# Microcontroller_Power.net
KiCad netlist of a schematic drawn in Altium Designer
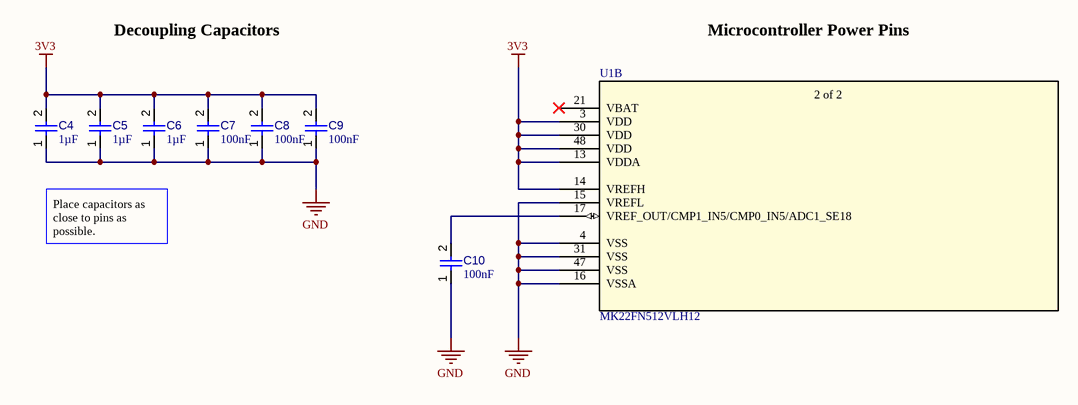
[diagram p0: Microcontroller_Power.SchDoc]

(export (version "E")
  (design (tool "Eeschema 10.0.6"))
  (components
    (comp (ref "C4")
      (value "1µF")
      (footprint "CAPC0805(2012)145_L")
      (description "Chip Capacitor, 1µF +/-20%, 25V, 0805, Thickness 1.45 mm")
      (fields (field (name "TOLERANCE") "10%") (field (name "Comment") "Capacitor 1µF +/-20% 25V 0805"))
      (libsource (lib "James Cook University") (part "CAP-NP-2"))
    )
    (comp (ref "C5")
      (value "1µF")
      (footprint "CAPC0805(2012)145_L")
      (description "Chip Capacitor, 1µF +/-20%, 25V, 0805, Thickness 1.45 mm")
      (fields (field (name "TOLERANCE") "10%") (field (name "Comment") "Capacitor 1µF +/-20% 25V 0805"))
      (libsource (lib "James Cook University") (part "CAP-NP-2"))
    )
    (comp (ref "C6")
      (value "1µF")
      (footprint "CAPC0805(2012)145_L")
      (description "Chip Capacitor, 1µF +/-20%, 25V, 0805, Thickness 1.45 mm")
      (fields (field (name "TOLERANCE") "10%") (field (name "Comment") "Capacitor 1µF +/-20% 25V 0805"))
      (libsource (lib "James Cook University") (part "CAP-NP-2"))
    )
    (comp (ref "C7")
      (value "100nF")
      (footprint "CAPC0805(2012)145_L")
      (description "Chip Capacitor, 100nF +/-20%, 25V, 0805, Thickness 1.45 mm")
      (fields (field (name "TOLERANCE") "10%") (field (name "Comment") "Capacitor 100nF +/-20% 25V 0805"))
      (libsource (lib "James Cook University") (part "CAP-NP-2"))
    )
    (comp (ref "C8")
      (value "100nF")
      (footprint "CAPC0805(2012)145_L")
      (description "Chip Capacitor, 100nF +/-20%, 25V, 0805, Thickness 1.45 mm")
      (fields (field (name "TOLERANCE") "10%") (field (name "Comment") "Capacitor 100nF +/-20% 25V 0805"))
      (libsource (lib "James Cook University") (part "CAP-NP-2"))
    )
    (comp (ref "C9")
      (value "100nF")
      (footprint "CAPC0805(2012)145_L")
      (description "Chip Capacitor, 100nF +/-20%, 25V, 0805, Thickness 1.45 mm")
      (fields (field (name "TOLERANCE") "10%") (field (name "Comment") "Capacitor 100nF +/-20% 25V 0805"))
      (libsource (lib "James Cook University") (part "CAP-NP-2"))
    )
    (comp (ref "C10")
      (value "100nF")
      (footprint "CAPC0805(2012)145_L")
      (description "Chip Capacitor, 100nF +/-20%, 25V, 0805, Thickness 1.45 mm")
      (fields (field (name "TOLERANCE") "10%") (field (name "Comment") "Capacitor 100nF +/-20% 25V 0805"))
      (libsource (lib "James Cook University") (part "CAP-NP-2"))
    )
    (comp (ref "U1")
      (value "MK22FN512VLH12")
      (footprint "LQFP-64_10X10X1.6_NXP")
      (description "No Description Available")
      (fields (field (name "COPYRIGHT") "Copyright (C) 2016 Accelerated Designs. All rights reserved"))
      (libsource (lib "MK22FN512VLH12") (part "MK22FN512VLH12"))
    )
  )
  (nets
    (net (code "1") (name "3V3") (class "Default")
      (node (ref "C4") (pin "2") (pinfunction "2_2") (pintype "passive"))
      (node (ref "C5") (pin "2") (pinfunction "2_2") (pintype "passive"))
      (node (ref "C6") (pin "2") (pinfunction "2_2") (pintype "passive"))
      (node (ref "C7") (pin "2") (pinfunction "2_2") (pintype "passive"))
      (node (ref "C8") (pin "2") (pinfunction "2_2") (pintype "passive"))
      (node (ref "C9") (pin "2") (pinfunction "2_2") (pintype "passive"))
      (node (ref "U1") (pin "13") (pinfunction "VDDA_13") (pintype "power_in"))
      (node (ref "U1") (pin "14") (pinfunction "VREFH_14") (pintype "power_in"))
      (node (ref "U1") (pin "3") (pinfunction "VDD_3") (pintype "power_in"))
      (node (ref "U1") (pin "30") (pinfunction "VDD_30") (pintype "power_in"))
      (node (ref "U1") (pin "48") (pinfunction "VDD_48") (pintype "power_in"))
    )
    (net (code "2") (name "GND") (class "Default")
      (node (ref "C10") (pin "1") (pinfunction "1_1") (pintype "passive"))
      (node (ref "C4") (pin "1") (pinfunction "1_1") (pintype "passive"))
      (node (ref "C5") (pin "1") (pinfunction "1_1") (pintype "passive"))
      (node (ref "C6") (pin "1") (pinfunction "1_1") (pintype "passive"))
      (node (ref "C7") (pin "1") (pinfunction "1_1") (pintype "passive"))
      (node (ref "C8") (pin "1") (pinfunction "1_1") (pintype "passive"))
      (node (ref "C9") (pin "1") (pinfunction "1_1") (pintype "passive"))
      (node (ref "U1") (pin "15") (pinfunction "VREFL_15") (pintype "power_in"))
      (node (ref "U1") (pin "16") (pinfunction "VSSA_16") (pintype "power_in"))
      (node (ref "U1") (pin "31") (pinfunction "VSS_31") (pintype "power_in"))
      (node (ref "U1") (pin "4") (pinfunction "VSS_4") (pintype "power_in"))
      (node (ref "U1") (pin "47") (pinfunction "VSS_47") (pintype "power_in"))
    )
    (net (code "3") (name "Net-(U1B-VREF_OUT{slash}CMP1_IN5{slash}CMP0_IN5{slash}ADC1_SE18)") (class "Default")
      (node (ref "C10") (pin "2") (pinfunction "2_2") (pintype "passive"))
      (node (ref "U1") (pin "17") (pinfunction "VREF_OUT/CMP1_IN5/CMP0_IN5/ADC1_SE18_17") (pintype "bidirectional"))
    )
    (net (code "4") (name "unconnected-(U1B-VBAT-Pad21)") (class "Default")
      (node (ref "U1") (pin "21") (pinfunction "VBAT_21") (pintype "power_in+no_connect"))
    )
  )
)
